# Headphone_Amplifier.net
KiCad netlist of a schematic drawn in EAGLE
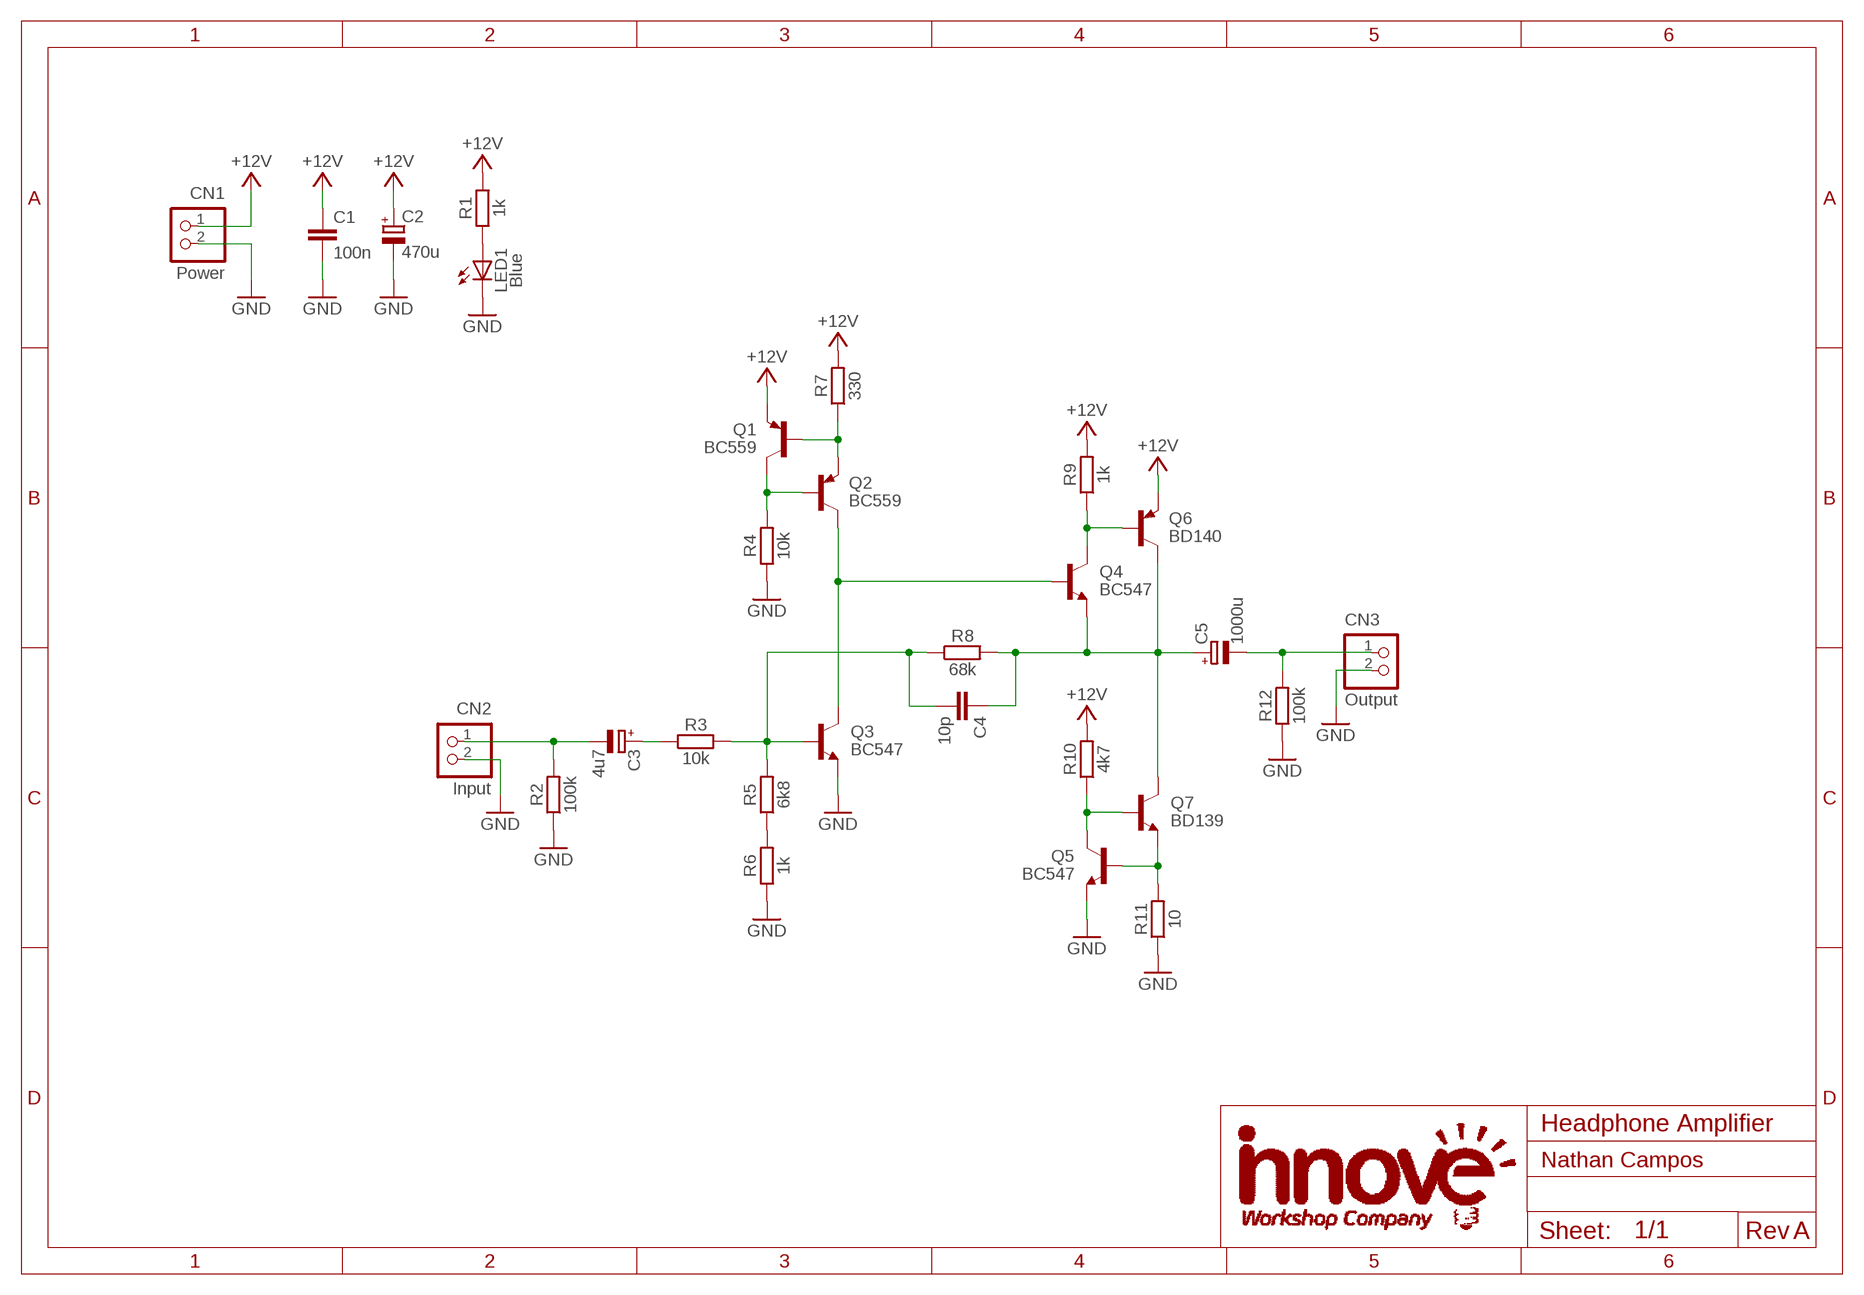
[diagram p0: schematic, sheet 1]

(export (version "E")
  (design (tool "Eeschema 10.0.6"))
  (components
    (comp (ref "C1")
      (value "100n")
      (footprint "eagle-import:C050-025X075")
      (libsource (lib "eagle-import") (part "C5.0-2.5X7.5"))
    )
    (comp (ref "C2")
      (value "470u")
      (footprint "eagle-import:E5-10")
      (libsource (lib "eagle-import") (part "CPOL-E5-10"))
    )
    (comp (ref "C3")
      (value "4u7")
      (footprint "eagle-import:E1,8-4")
      (libsource (lib "eagle-import") (part "CPOL-E1.8-4"))
    )
    (comp (ref "C4")
      (value "10p")
      (footprint "eagle-import:C050-025X075")
      (libsource (lib "eagle-import") (part "C5.0-2.5X7.5"))
    )
    (comp (ref "C5")
      (value "1000u")
      (footprint "eagle-import:E5-10")
      (libsource (lib "eagle-import") (part "CPOL-E5-10"))
    )
    (comp (ref "CN1")
      (value "Power")
      (footprint "eagle-import:B2B-XH-A")
      (libsource (lib "eagle-import") (part "B2B-XH-A"))
    )
    (comp (ref "CN2")
      (value "Input")
      (footprint "eagle-import:B2B-XH-A")
      (libsource (lib "eagle-import") (part "B2B-XH-A"))
    )
    (comp (ref "CN3")
      (value "Output")
      (footprint "eagle-import:B2B-XH-A")
      (libsource (lib "eagle-import") (part "B2B-XH-A"))
    )
    (comp (ref "LED1")
      (value "Blue")
      (footprint "eagle-import:LED5MM")
      (libsource (lib "eagle-import") (part "LED5MM"))
    )
    (comp (ref "Q1")
      (value "BC559")
      (footprint "eagle-import:TO92")
      (libsource (lib "eagle-import") (part "BC559"))
    )
    (comp (ref "Q2")
      (value "BC559")
      (footprint "eagle-import:TO92")
      (libsource (lib "eagle-import") (part "BC559"))
    )
    (comp (ref "Q3")
      (value "BC547")
      (footprint "eagle-import:TO92")
      (libsource (lib "eagle-import") (part "BC547"))
    )
    (comp (ref "Q4")
      (value "BC547")
      (footprint "eagle-import:TO92")
      (libsource (lib "eagle-import") (part "BC547"))
    )
    (comp (ref "Q5")
      (value "BC547")
      (footprint "eagle-import:TO92")
      (libsource (lib "eagle-import") (part "BC547"))
    )
    (comp (ref "Q6")
      (value "BD140")
      (footprint "eagle-import:TO126V")
      (libsource (lib "eagle-import") (part "BD140"))
    )
    (comp (ref "Q7")
      (value "BD139")
      (footprint "eagle-import:TO126V")
      (libsource (lib "eagle-import") (part "BD139"))
    )
    (comp (ref "R1")
      (value "1k")
      (footprint "eagle-import:0207_10")
      (libsource (lib "eagle-import") (part "RT0207"))
    )
    (comp (ref "R2")
      (value "100k")
      (footprint "eagle-import:0207_10")
      (libsource (lib "eagle-import") (part "RT0207"))
    )
    (comp (ref "R3")
      (value "10k")
      (footprint "eagle-import:0207_10")
      (libsource (lib "eagle-import") (part "RT0207"))
    )
    (comp (ref "R4")
      (value "10k")
      (footprint "eagle-import:0207_10")
      (libsource (lib "eagle-import") (part "RT0207"))
    )
    (comp (ref "R5")
      (value "6k8")
      (footprint "eagle-import:0207_10")
      (libsource (lib "eagle-import") (part "RT0207"))
    )
    (comp (ref "R6")
      (value "1k")
      (footprint "eagle-import:0207_10")
      (libsource (lib "eagle-import") (part "RT0207"))
    )
    (comp (ref "R7")
      (value "330")
      (footprint "eagle-import:0207_10")
      (libsource (lib "eagle-import") (part "RT0207"))
    )
    (comp (ref "R8")
      (value "68k")
      (footprint "eagle-import:0207_10")
      (libsource (lib "eagle-import") (part "RT0207"))
    )
    (comp (ref "R9")
      (value "1k")
      (footprint "eagle-import:0207_10")
      (libsource (lib "eagle-import") (part "RT0207"))
    )
    (comp (ref "R10")
      (value "4k7")
      (footprint "eagle-import:0207_10")
      (libsource (lib "eagle-import") (part "RT0207"))
    )
    (comp (ref "R11")
      (value "10")
      (footprint "eagle-import:0207_10")
      (libsource (lib "eagle-import") (part "RT0207"))
    )
    (comp (ref "R12")
      (value "100k")
      (footprint "eagle-import:0207_10")
      (libsource (lib "eagle-import") (part "RT0207"))
    )
  )
  (nets
    (net (code "1") (name "+12V") (class "Default")
      (node (ref "C1") (pin "1") (pinfunction "1_1") (pintype "passive"))
      (node (ref "C2") (pin "+") (pinfunction "+_+") (pintype "passive"))
      (node (ref "CN1") (pin "1") (pinfunction "1_1") (pintype "passive"))
      (node (ref "Q1") (pin "3") (pinfunction "E_3") (pintype "passive"))
      (node (ref "Q6") (pin "1") (pinfunction "E_1") (pintype "passive"))
      (node (ref "R1") (pin "2") (pinfunction "2_2") (pintype "passive"))
      (node (ref "R10") (pin "2") (pinfunction "2_2") (pintype "passive"))
      (node (ref "R7") (pin "2") (pinfunction "2_2") (pintype "passive"))
      (node (ref "R9") (pin "2") (pinfunction "2_2") (pintype "passive"))
    )
    (net (code "2") (name "GND") (class "Default")
      (node (ref "C1") (pin "2") (pinfunction "2_2") (pintype "passive"))
      (node (ref "C2") (pin "-") (pinfunction "-_-") (pintype "passive"))
      (node (ref "CN1") (pin "2") (pinfunction "2_2") (pintype "passive"))
      (node (ref "CN2") (pin "2") (pinfunction "2_2") (pintype "passive"))
      (node (ref "CN3") (pin "2") (pinfunction "2_2") (pintype "passive"))
      (node (ref "LED1") (pin "K") (pinfunction "C_K") (pintype "passive"))
      (node (ref "Q3") (pin "3") (pinfunction "E_3") (pintype "passive"))
      (node (ref "Q5") (pin "3") (pinfunction "E_3") (pintype "passive"))
      (node (ref "R11") (pin "1") (pinfunction "1_1") (pintype "passive"))
      (node (ref "R12") (pin "1") (pinfunction "1_1") (pintype "passive"))
      (node (ref "R2") (pin "1") (pinfunction "1_1") (pintype "passive"))
      (node (ref "R4") (pin "1") (pinfunction "1_1") (pintype "passive"))
      (node (ref "R6") (pin "1") (pinfunction "1_1") (pintype "passive"))
    )
    (net (code "3") (name "Net-(C3-Pad+)") (class "Default")
      (node (ref "C3") (pin "+") (pinfunction "+_+") (pintype "passive"))
      (node (ref "R3") (pin "1") (pinfunction "1_1") (pintype "passive"))
    )
    (net (code "4") (name "Net-(C3-Pad-)") (class "Default")
      (node (ref "C3") (pin "-") (pinfunction "-_-") (pintype "passive"))
      (node (ref "CN2") (pin "1") (pinfunction "1_1") (pintype "passive"))
      (node (ref "R2") (pin "2") (pinfunction "2_2") (pintype "passive"))
    )
    (net (code "5") (name "Net-(C5-Pad-)") (class "Default")
      (node (ref "C5") (pin "-") (pinfunction "-_-") (pintype "passive"))
      (node (ref "CN3") (pin "1") (pinfunction "1_1") (pintype "passive"))
      (node (ref "R12") (pin "2") (pinfunction "2_2") (pintype "passive"))
    )
    (net (code "6") (name "Net-(LED1-PadA)") (class "Default")
      (node (ref "LED1") (pin "A") (pinfunction "A_A") (pintype "passive"))
      (node (ref "R1") (pin "1") (pinfunction "1_1") (pintype "passive"))
    )
    (net (code "7") (name "Net-(Q1-B)") (class "Default")
      (node (ref "Q1") (pin "2") (pinfunction "B_2") (pintype "passive"))
      (node (ref "Q2") (pin "3") (pinfunction "E_3") (pintype "passive"))
      (node (ref "R7") (pin "1") (pinfunction "1_1") (pintype "passive"))
    )
    (net (code "8") (name "Net-(Q1-C)") (class "Default")
      (node (ref "Q1") (pin "1") (pinfunction "C_1") (pintype "passive"))
      (node (ref "Q2") (pin "2") (pinfunction "B_2") (pintype "passive"))
      (node (ref "R4") (pin "2") (pinfunction "2_2") (pintype "passive"))
    )
    (net (code "9") (name "Net-(Q2-C)") (class "Default")
      (node (ref "Q2") (pin "1") (pinfunction "C_1") (pintype "passive"))
      (node (ref "Q3") (pin "1") (pinfunction "C_1") (pintype "passive"))
      (node (ref "Q4") (pin "2") (pinfunction "B_2") (pintype "passive"))
    )
    (net (code "10") (name "Net-(Q3-B)") (class "Default")
      (node (ref "C4") (pin "2") (pinfunction "2_2") (pintype "passive"))
      (node (ref "Q3") (pin "2") (pinfunction "B_2") (pintype "passive"))
      (node (ref "R3") (pin "2") (pinfunction "2_2") (pintype "passive"))
      (node (ref "R5") (pin "2") (pinfunction "2_2") (pintype "passive"))
      (node (ref "R8") (pin "1") (pinfunction "1_1") (pintype "passive"))
    )
    (net (code "11") (name "Net-(Q4-C)") (class "Default")
      (node (ref "Q4") (pin "1") (pinfunction "C_1") (pintype "passive"))
      (node (ref "Q6") (pin "3") (pinfunction "B_3") (pintype "passive"))
      (node (ref "R9") (pin "1") (pinfunction "1_1") (pintype "passive"))
    )
    (net (code "12") (name "Net-(Q4-E)") (class "Default")
      (node (ref "C4") (pin "1") (pinfunction "1_1") (pintype "passive"))
      (node (ref "C5") (pin "+") (pinfunction "+_+") (pintype "passive"))
      (node (ref "Q4") (pin "3") (pinfunction "E_3") (pintype "passive"))
      (node (ref "Q6") (pin "2") (pinfunction "C_2") (pintype "passive"))
      (node (ref "Q7") (pin "2") (pinfunction "C_2") (pintype "passive"))
      (node (ref "R8") (pin "2") (pinfunction "2_2") (pintype "passive"))
    )
    (net (code "13") (name "Net-(Q5-B)") (class "Default")
      (node (ref "Q5") (pin "2") (pinfunction "B_2") (pintype "passive"))
      (node (ref "Q7") (pin "1") (pinfunction "E_1") (pintype "passive"))
      (node (ref "R11") (pin "2") (pinfunction "2_2") (pintype "passive"))
    )
    (net (code "14") (name "Net-(Q5-C)") (class "Default")
      (node (ref "Q5") (pin "1") (pinfunction "C_1") (pintype "passive"))
      (node (ref "Q7") (pin "3") (pinfunction "B_3") (pintype "passive"))
      (node (ref "R10") (pin "1") (pinfunction "1_1") (pintype "passive"))
    )
    (net (code "15") (name "Net-(R5-Pad1)") (class "Default")
      (node (ref "R5") (pin "1") (pinfunction "1_1") (pintype "passive"))
      (node (ref "R6") (pin "2") (pinfunction "2_2") (pintype "passive"))
    )
  )
)
